# Mechanicals.net
KiCad netlist of a schematic drawn in Altium Designer
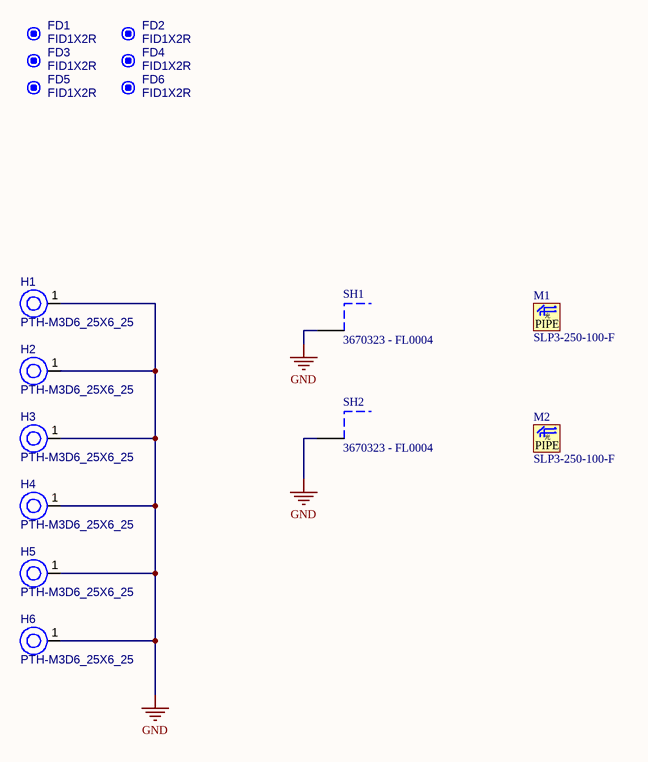
[diagram p0: Mechanicals.SchDoc]

(export (version "E")
  (design (tool "Eeschema 10.0.6"))
  (components
    (comp (ref "FD1")
      (value "FID1X2R")
      (footprint "FID1X2R")
      (description "Fiducial - Round 1x2mm")
      (libsource (lib "Flycatcher Labs") (part "CMP-00134-2"))
    )
    (comp (ref "FD2")
      (value "FID1X2R")
      (footprint "FID1X2R")
      (description "Fiducial - Round 1x2mm")
      (libsource (lib "Flycatcher Labs") (part "CMP-00134-2"))
    )
    (comp (ref "FD3")
      (value "FID1X2R")
      (footprint "FID1X2R")
      (description "Fiducial - Round 1x2mm")
      (libsource (lib "Flycatcher Labs") (part "CMP-00134-2"))
    )
    (comp (ref "FD4")
      (value "FID1X2R")
      (footprint "FID1X2R")
      (description "Fiducial - Round 1x2mm")
      (libsource (lib "Flycatcher Labs") (part "CMP-00134-2"))
    )
    (comp (ref "FD5")
      (value "FID1X2R")
      (footprint "FID1X2R")
      (description "Fiducial - Round 1x2mm")
      (libsource (lib "Flycatcher Labs") (part "CMP-00134-2"))
    )
    (comp (ref "FD6")
      (value "FID1X2R")
      (footprint "FID1X2R")
      (description "Fiducial - Round 1x2mm")
      (libsource (lib "Flycatcher Labs") (part "CMP-00134-2"))
    )
    (comp (ref "H1")
      (value "PTH-M3D6_25X6_25")
      (footprint "PTH-M3D6_25X6_25")
      (description "M3 PTH (3mm), 6.25mm pad")
      (libsource (lib "Flycatcher Labs") (part "CMP-00028-00000-1"))
    )
    (comp (ref "H2")
      (value "PTH-M3D6_25X6_25")
      (footprint "PTH-M3D6_25X6_25")
      (description "M3 PTH (3mm), 6.25mm pad")
      (libsource (lib "Flycatcher Labs") (part "CMP-00028-00000-1"))
    )
    (comp (ref "H3")
      (value "PTH-M3D6_25X6_25")
      (footprint "PTH-M3D6_25X6_25")
      (description "M3 PTH (3mm), 6.25mm pad")
      (libsource (lib "Flycatcher Labs") (part "CMP-00028-00000-1"))
    )
    (comp (ref "H4")
      (value "PTH-M3D6_25X6_25")
      (footprint "PTH-M3D6_25X6_25")
      (description "M3 PTH (3mm), 6.25mm pad")
      (libsource (lib "Flycatcher Labs") (part "CMP-00028-00000-1"))
    )
    (comp (ref "H5")
      (value "PTH-M3D6_25X6_25")
      (footprint "PTH-M3D6_25X6_25")
      (description "M3 PTH (3mm), 6.25mm pad")
      (libsource (lib "Flycatcher Labs") (part "CMP-00028-00000-1"))
    )
    (comp (ref "H6")
      (value "PTH-M3D6_25X6_25")
      (footprint "PTH-M3D6_25X6_25")
      (description "M3 PTH (3mm), 6.25mm pad")
      (libsource (lib "Flycatcher Labs") (part "CMP-00028-00000-1"))
    )
    (comp (ref "M1")
      (value "SLP3-250-100-F")
      (footprint "BIVAR SLP3-250-100-F")
      (description "LIGHT PIPE CLEAR 3MM LENS R/A")
      (fields (field (name "MANUFACTURER") "Bivar Inc."))
      (libsource (lib "Celestial Altium Library - altium_library") (part "Light Pipe"))
    )
    (comp (ref "M2")
      (value "SLP3-250-100-F")
      (footprint "BIVAR SLP3-250-100-F")
      (description "LIGHT PIPE CLEAR 3MM LENS R/A")
      (fields (field (name "MANUFACTURER") "Bivar Inc."))
      (libsource (lib "Celestial Altium Library - altium_library") (part "Light Pipe"))
    )
    (comp (ref "SH1")
      (value "3670323 - FL0004")
      (footprint "3670323 - FL-0004")
      (description "Shield Cabinet Frame, 32.3mm X 23.8mm Wurth Elektronik 3670323 - modified footprint for FL-0004")
      (libsource (lib "Flycatcher Labs") (part "WE-SHC"))
    )
    (comp (ref "SH2")
      (value "3670323 - FL0004")
      (footprint "3670323 - FL-0004")
      (description "Shield Cabinet Frame, 32.3mm X 23.8mm Wurth Elektronik 3670323 - modified footprint for FL-0004")
      (libsource (lib "Flycatcher Labs") (part "WE-SHC"))
    )
  )
  (nets
    (net (code "1") (name "GND") (class "Default")
      (node (ref "H1") (pin "1") (pinfunction "H1_1") (pintype "passive"))
      (node (ref "H2") (pin "1") (pinfunction "H1_1") (pintype "passive"))
      (node (ref "H3") (pin "1") (pinfunction "H1_1") (pintype "passive"))
      (node (ref "H4") (pin "1") (pinfunction "H1_1") (pintype "passive"))
      (node (ref "H5") (pin "1") (pinfunction "H1_1") (pintype "passive"))
      (node (ref "H6") (pin "1") (pinfunction "H1_1") (pintype "passive"))
      (node (ref "SH1") (pin "1") (pinfunction "1_1") (pintype "passive"))
      (node (ref "SH2") (pin "1") (pinfunction "1_1") (pintype "passive"))
    )
  )
)
